# display.net
KiCad netlist of a schematic drawn in Altium Designer
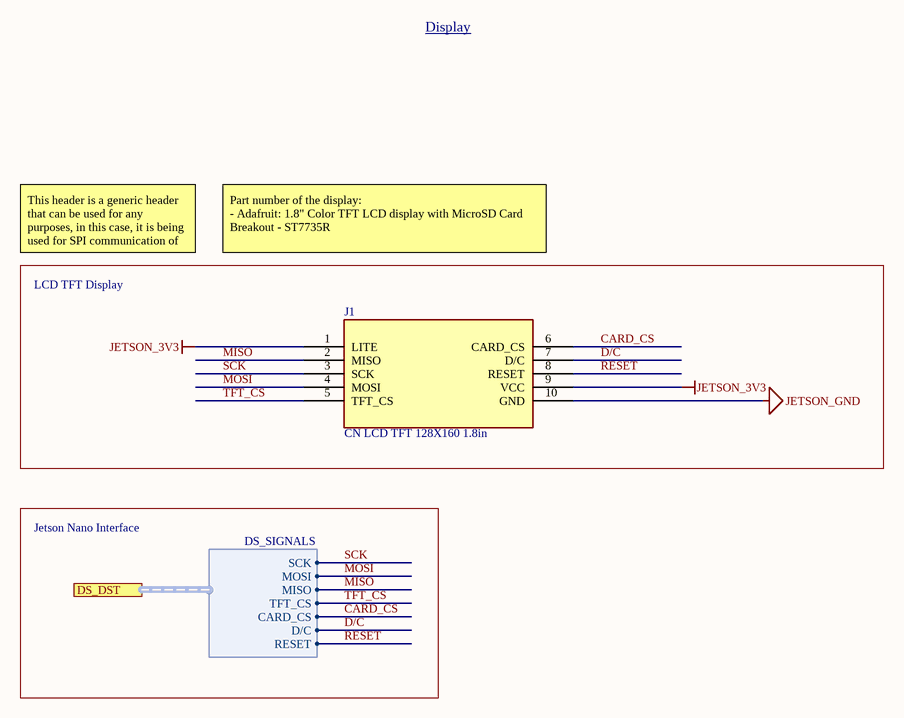
[diagram p0: display.SchDoc]

(export (version "E")
  (design (tool "Eeschema 10.0.6"))
  (components
    (comp (ref "J1")
      (value "CN LCD TFT 128X160 1.8in")
      (footprint "CN LCD TFT 128X160 1.8in")
      (libsource (lib "Connector_Library") (part "CN LCD TFT 128X160 1.8in"))
    )
  )
  (nets
    (net (code "2") (name "/CARD_CS") (class "Default")
      (node (ref "J1") (pin "6") (pinfunction "CARD_CS_6") (pintype "passive"))
    )
    (net (code "3") (name "/D{slash}C") (class "Default")
      (node (ref "J1") (pin "7") (pinfunction "D/C_7") (pintype "passive"))
    )
    (net (code "4") (name "/MISO") (class "Default")
      (node (ref "J1") (pin "2") (pinfunction "MISO_2") (pintype "passive"))
    )
    (net (code "5") (name "/MOSI") (class "Default")
      (node (ref "J1") (pin "4") (pinfunction "MOSI_4") (pintype "passive"))
    )
    (net (code "6") (name "/RESET") (class "Default")
      (node (ref "J1") (pin "8") (pinfunction "RESET_8") (pintype "passive"))
    )
    (net (code "7") (name "/SCK") (class "Default")
      (node (ref "J1") (pin "3") (pinfunction "SCK_3") (pintype "passive"))
    )
    (net (code "8") (name "/TFT_CS") (class "Default")
      (node (ref "J1") (pin "5") (pinfunction "TFT_CS_5") (pintype "passive"))
    )
    (net (code "10") (name "JETSON_3V3") (class "Default")
      (node (ref "J1") (pin "1") (pinfunction "LITE_1") (pintype "passive"))
      (node (ref "J1") (pin "9") (pinfunction "VCC_9") (pintype "passive"))
    )
    (net (code "11") (name "JETSON_GND") (class "Default")
      (node (ref "J1") (pin "10") (pinfunction "GND_10") (pintype "passive"))
    )
  )
)
